# rts.net
KiCad netlist of a schematic drawn in EAGLE
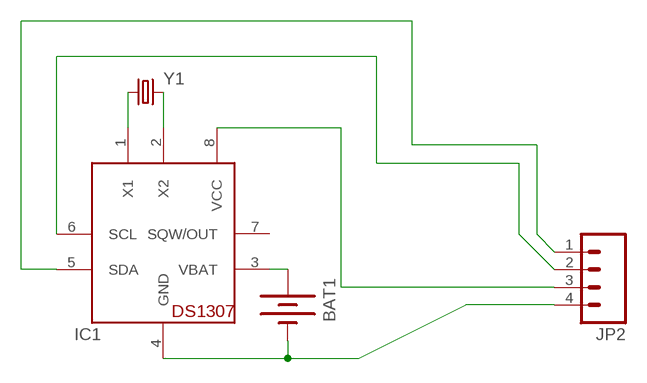
[diagram p0: schematic, sheet 1]

(export (version "E")
  (design (tool "Eeschema 10.0.6"))
  (components
    (comp (ref "BAT1")
      (value "BATTERYFOB")
      (footprint "eagle-import:BATTERY_20MM_PTH_COMPACT")
      (libsource (lib "eagle-import") (part "BATTERYFOB"))
    )
    (comp (ref "IC1")
      (value "DS1307")
      (footprint "eagle-import:DIL08")
      (libsource (lib "eagle-import") (part "DS1307"))
    )
    (comp (ref "JP2")
      (value "M04LONGPADS")
      (footprint "eagle-import:1X04_LONGPADS")
      (libsource (lib "eagle-import") (part "M04LONGPADS"))
    )
    (comp (ref "Y1")
      (value "CRYSTALTC38H")
      (footprint "eagle-import:TC38H")
      (libsource (lib "eagle-import") (part "CRYSTALTC38H"))
    )
  )
  (nets
    (net (code "1") (name "Net-(BAT1-+)") (class "Default")
      (node (ref "BAT1") (pin "1") (pinfunction "+_1") (pintype "power_in"))
      (node (ref "IC1") (pin "3") (pinfunction "VBAT_3") (pintype "power_in"))
    )
    (net (code "2") (name "Net-(BAT1--)") (class "Default")
      (node (ref "BAT1") (pin "2") (pinfunction "-_2") (pintype "power_in"))
      (node (ref "IC1") (pin "4") (pinfunction "GND_4") (pintype "power_in"))
      (node (ref "JP2") (pin "4") (pinfunction "4_4") (pintype "passive"))
    )
    (net (code "3") (name "Net-(IC1-SCL)") (class "Default")
      (node (ref "IC1") (pin "6") (pinfunction "SCL_6") (pintype "bidirectional"))
      (node (ref "JP2") (pin "2") (pinfunction "2_2") (pintype "passive"))
    )
    (net (code "4") (name "Net-(IC1-SDA)") (class "Default")
      (node (ref "IC1") (pin "5") (pinfunction "SDA_5") (pintype "bidirectional"))
      (node (ref "JP2") (pin "1") (pinfunction "1_1") (pintype "passive"))
    )
    (net (code "5") (name "Net-(IC1-VCC)") (class "Default")
      (node (ref "IC1") (pin "8") (pinfunction "VCC_8") (pintype "power_in"))
      (node (ref "JP2") (pin "3") (pinfunction "3_3") (pintype "passive"))
    )
    (net (code "6") (name "Net-(IC1-X1)") (class "Default")
      (node (ref "IC1") (pin "1") (pinfunction "X1_1") (pintype "passive"))
      (node (ref "Y1") (pin "1") (pinfunction "1_1") (pintype "passive"))
    )
    (net (code "7") (name "Net-(IC1-X2)") (class "Default")
      (node (ref "IC1") (pin "2") (pinfunction "X2_2") (pintype "passive"))
      (node (ref "Y1") (pin "2") (pinfunction "2_2") (pintype "passive"))
    )
    (net (code "8") (name "unconnected-(IC1-SQW{slash}OUT-Pad7)") (class "Default")
      (node (ref "IC1") (pin "7") (pinfunction "SQW/OUT_7") (pintype "bidirectional"))
    )
  )
)
